# joysticks_right.net
KiCad netlist of a schematic drawn in EAGLE
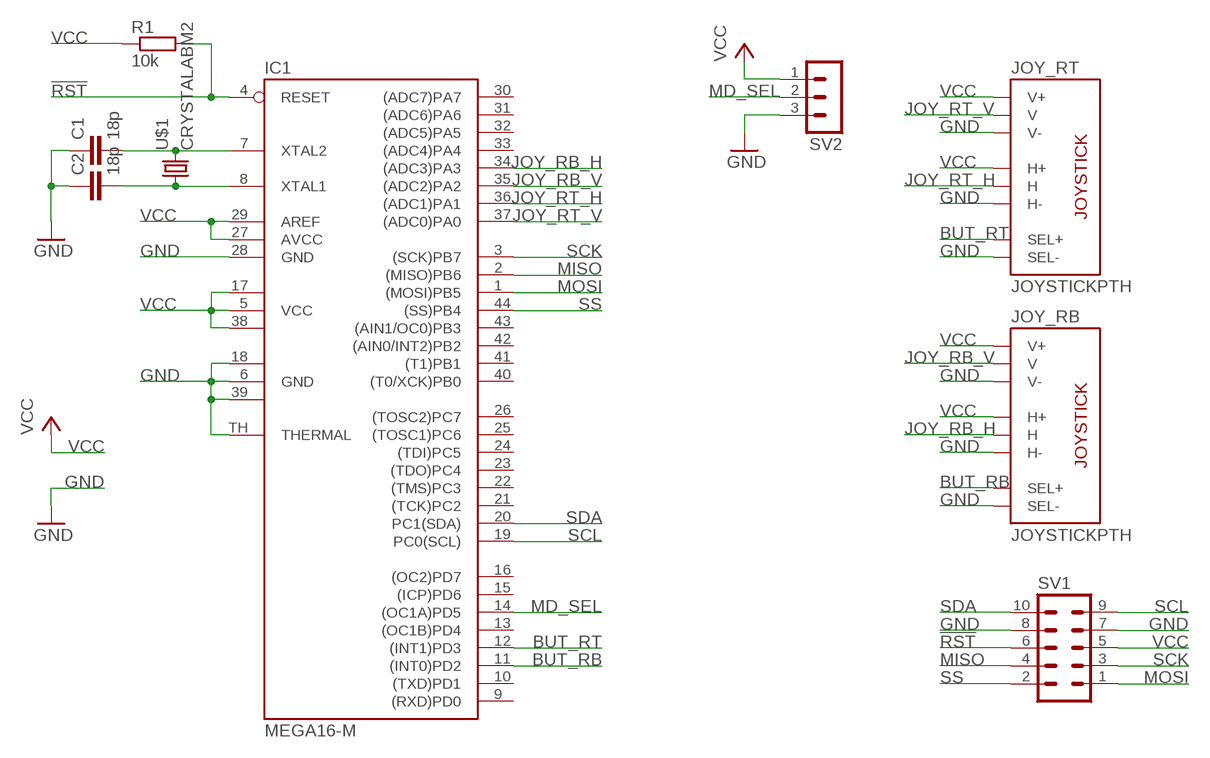
[diagram p0: schematic, sheet 1]

(export (version "E")
  (design (tool "Eeschema 10.0.6"))
  (components
    (comp (ref "C1")
      (value "18p")
      (footprint "eagle-import:C0603")
      (libsource (lib "eagle-import") (part "C-EUC0603"))
    )
    (comp (ref "C2")
      (value "18p")
      (footprint "eagle-import:C0603")
      (libsource (lib "eagle-import") (part "C-EUC0603"))
    )
    (comp (ref "IC1")
      (value "MEGA16-M")
      (footprint "eagle-import:MLF44-TH")
      (fields (field (name "MPN") "ATMEGA16-16MU"))
      (libsource (lib "eagle-import") (part "MEGA16-M"))
    )
    (comp (ref "JOY_RB")
      (value "JOYSTICKPTH")
      (footprint "eagle-import:JOYSTICK")
      (libsource (lib "eagle-import") (part "JOYSTICKPTH"))
    )
    (comp (ref "JOY_RT")
      (value "JOYSTICKPTH")
      (footprint "eagle-import:JOYSTICK")
      (libsource (lib "eagle-import") (part "JOYSTICKPTH"))
    )
    (comp (ref "R1")
      (value "10k")
      (footprint "eagle-import:R0603")
      (libsource (lib "eagle-import") (part "R-EU_R0603"))
    )
    (comp (ref "SV1")
      (value "MA05-2")
      (footprint "eagle-import:MA05-2")
      (libsource (lib "eagle-import") (part "MA05-2"))
    )
    (comp (ref "SV2")
      (value "MA03-1")
      (footprint "eagle-import:MA03-1")
      (libsource (lib "eagle-import") (part "MA03-1"))
    )
    (comp (ref "U$1")
      (value "CRYSTALABM2")
      (footprint "eagle-import:ABM2")
      (libsource (lib "eagle-import") (part "CRYSTALABM2"))
    )
  )
  (nets
    (net (code "1") (name "/BUT_RB") (class "Default")
      (node (ref "IC1") (pin "11") (pinfunction "(INT0)PD2_11") (pintype "bidirectional"))
      (node (ref "JOY_RB") (pin "B1A") (pinfunction "SEL+_B1A") (pintype "bidirectional"))
    )
    (net (code "2") (name "/BUT_RT") (class "Default")
      (node (ref "IC1") (pin "12") (pinfunction "(INT1)PD3_12") (pintype "bidirectional"))
      (node (ref "JOY_RT") (pin "B1A") (pinfunction "SEL+_B1A") (pintype "bidirectional"))
    )
    (net (code "3") (name "/JOY_RB_H") (class "Default")
      (node (ref "IC1") (pin "34") (pinfunction "(ADC3)PA3_34") (pintype "bidirectional"))
      (node (ref "JOY_RB") (pin "H2") (pinfunction "H_H2") (pintype "bidirectional"))
    )
    (net (code "4") (name "/JOY_RB_V") (class "Default")
      (node (ref "IC1") (pin "35") (pinfunction "(ADC2)PA2_35") (pintype "bidirectional"))
      (node (ref "JOY_RB") (pin "V2") (pinfunction "V_V2") (pintype "bidirectional"))
    )
    (net (code "5") (name "/JOY_RT_H") (class "Default")
      (node (ref "IC1") (pin "36") (pinfunction "(ADC1)PA1_36") (pintype "bidirectional"))
      (node (ref "JOY_RT") (pin "H2") (pinfunction "H_H2") (pintype "bidirectional"))
    )
    (net (code "6") (name "/JOY_RT_V") (class "Default")
      (node (ref "IC1") (pin "37") (pinfunction "(ADC0)PA0_37") (pintype "bidirectional"))
      (node (ref "JOY_RT") (pin "V2") (pinfunction "V_V2") (pintype "bidirectional"))
    )
    (net (code "7") (name "/MD_SEL") (class "Default")
      (node (ref "IC1") (pin "14") (pinfunction "(OC1A)PD5_14") (pintype "bidirectional"))
      (node (ref "SV2") (pin "2") (pinfunction "2_2") (pintype "passive"))
    )
    (net (code "8") (name "/MISO") (class "Default")
      (node (ref "IC1") (pin "2") (pinfunction "(MISO)PB6_2") (pintype "bidirectional"))
      (node (ref "SV1") (pin "4") (pinfunction "4_4") (pintype "passive"))
    )
    (net (code "9") (name "/MOSI") (class "Default")
      (node (ref "IC1") (pin "1") (pinfunction "(MOSI)PB5_1") (pintype "bidirectional"))
      (node (ref "SV1") (pin "1") (pinfunction "1_1") (pintype "passive"))
    )
    (net (code "10") (name "/SCK") (class "Default")
      (node (ref "IC1") (pin "3") (pinfunction "(SCK)PB7_3") (pintype "bidirectional"))
      (node (ref "SV1") (pin "3") (pinfunction "3_3") (pintype "passive"))
    )
    (net (code "11") (name "/SCL") (class "Default")
      (node (ref "IC1") (pin "19") (pinfunction "PC0(SCL)_19") (pintype "bidirectional"))
      (node (ref "SV1") (pin "9") (pinfunction "9_9") (pintype "passive"))
    )
    (net (code "12") (name "/SDA") (class "Default")
      (node (ref "IC1") (pin "20") (pinfunction "PC1(SDA)_20") (pintype "bidirectional"))
      (node (ref "SV1") (pin "10") (pinfunction "10_10") (pintype "passive"))
    )
    (net (code "13") (name "/SS") (class "Default")
      (node (ref "IC1") (pin "44") (pinfunction "(SS)PB4_44") (pintype "bidirectional"))
      (node (ref "SV1") (pin "2") (pinfunction "2_2") (pintype "passive"))
    )
    (net (code "14") (name "/~{RST}") (class "Default")
      (node (ref "IC1") (pin "4") (pinfunction "RESET_4") (pintype "input"))
      (node (ref "R1") (pin "2") (pinfunction "2_2") (pintype "passive"))
      (node (ref "SV1") (pin "6") (pinfunction "6_6") (pintype "passive"))
    )
    (net (code "15") (name "GND") (class "Default")
      (node (ref "C1") (pin "1") (pinfunction "1_1") (pintype "passive"))
      (node (ref "C2") (pin "1") (pinfunction "1_1") (pintype "passive"))
      (node (ref "IC1") (pin "18") (pinfunction "GND1_18") (pintype "power_in"))
      (node (ref "IC1") (pin "28") (pinfunction "GND_28") (pintype "power_in"))
      (node (ref "IC1") (pin "39") (pinfunction "GND2_39") (pintype "power_in"))
      (node (ref "IC1") (pin "6") (pinfunction "GND_6") (pintype "power_in"))
      (node (ref "IC1") (pin "TH") (pinfunction "THERMAL_TH") (pintype "input"))
      (node (ref "JOY_RB") (pin "B2A") (pinfunction "SEL-_B2A") (pintype "bidirectional"))
      (node (ref "JOY_RB") (pin "H3") (pinfunction "H-_H3") (pintype "bidirectional"))
      (node (ref "JOY_RB") (pin "V3") (pinfunction "V-_V3") (pintype "bidirectional"))
      (node (ref "JOY_RT") (pin "B2A") (pinfunction "SEL-_B2A") (pintype "bidirectional"))
      (node (ref "JOY_RT") (pin "H3") (pinfunction "H-_H3") (pintype "bidirectional"))
      (node (ref "JOY_RT") (pin "V3") (pinfunction "V-_V3") (pintype "bidirectional"))
      (node (ref "SV1") (pin "7") (pinfunction "7_7") (pintype "passive"))
      (node (ref "SV1") (pin "8") (pinfunction "8_8") (pintype "passive"))
      (node (ref "SV2") (pin "3") (pinfunction "3_3") (pintype "passive"))
    )
    (net (code "16") (name "Net-(IC1-XTAL1)") (class "Default")
      (node (ref "C2") (pin "2") (pinfunction "2_2") (pintype "passive"))
      (node (ref "IC1") (pin "8") (pinfunction "XTAL1_8") (pintype "bidirectional"))
      (node (ref "U$1") (pin "P$1") (pinfunction "1_P$1") (pintype "passive"))
    )
    (net (code "17") (name "Net-(IC1-XTAL2)") (class "Default")
      (node (ref "C1") (pin "2") (pinfunction "2_2") (pintype "passive"))
      (node (ref "IC1") (pin "7") (pinfunction "XTAL2_7") (pintype "bidirectional"))
      (node (ref "U$1") (pin "P$2") (pinfunction "2_P$2") (pintype "passive"))
    )
    (net (code "18") (name "VCC") (class "Default")
      (node (ref "IC1") (pin "17") (pinfunction "VCC1_17") (pintype "power_in"))
      (node (ref "IC1") (pin "27") (pinfunction "AVCC_27") (pintype "power_in"))
      (node (ref "IC1") (pin "29") (pinfunction "AREF_29") (pintype "passive"))
      (node (ref "IC1") (pin "38") (pinfunction "VCC2_38") (pintype "power_in"))
      (node (ref "IC1") (pin "5") (pinfunction "VCC_5") (pintype "power_in"))
      (node (ref "JOY_RB") (pin "H1") (pinfunction "H+_H1") (pintype "bidirectional"))
      (node (ref "JOY_RB") (pin "V1") (pinfunction "V+_V1") (pintype "bidirectional"))
      (node (ref "JOY_RT") (pin "H1") (pinfunction "H+_H1") (pintype "bidirectional"))
      (node (ref "JOY_RT") (pin "V1") (pinfunction "V+_V1") (pintype "bidirectional"))
      (node (ref "R1") (pin "1") (pinfunction "1_1") (pintype "passive"))
      (node (ref "SV1") (pin "5") (pinfunction "5_5") (pintype "passive"))
      (node (ref "SV2") (pin "1") (pinfunction "1_1") (pintype "passive"))
    )
    (net (code "19") (name "unconnected-(IC1-(ADC4)PA4-Pad33)") (class "Default")
      (node (ref "IC1") (pin "33") (pinfunction "(ADC4)PA4_33") (pintype "bidirectional"))
    )
    (net (code "20") (name "unconnected-(IC1-(ADC5)PA5-Pad32)") (class "Default")
      (node (ref "IC1") (pin "32") (pinfunction "(ADC5)PA5_32") (pintype "bidirectional"))
    )
    (net (code "21") (name "unconnected-(IC1-(ADC6)PA6-Pad31)") (class "Default")
      (node (ref "IC1") (pin "31") (pinfunction "(ADC6)PA6_31") (pintype "bidirectional"))
    )
    (net (code "22") (name "unconnected-(IC1-(ADC7)PA7-Pad30)") (class "Default")
      (node (ref "IC1") (pin "30") (pinfunction "(ADC7)PA7_30") (pintype "bidirectional"))
    )
    (net (code "23") (name "unconnected-(IC1-(AIN0{slash}INT2)PB2-Pad42)") (class "Default")
      (node (ref "IC1") (pin "42") (pinfunction "(AIN0/INT2)PB2_42") (pintype "bidirectional"))
    )
    (net (code "24") (name "unconnected-(IC1-(AIN1{slash}OC0)PB3-Pad43)") (class "Default")
      (node (ref "IC1") (pin "43") (pinfunction "(AIN1/OC0)PB3_43") (pintype "bidirectional"))
    )
    (net (code "25") (name "unconnected-(IC1-(ICP)PD6-Pad15)") (class "Default")
      (node (ref "IC1") (pin "15") (pinfunction "(ICP)PD6_15") (pintype "bidirectional"))
    )
    (net (code "26") (name "unconnected-(IC1-(OC1B)PD4-Pad13)") (class "Default")
      (node (ref "IC1") (pin "13") (pinfunction "(OC1B)PD4_13") (pintype "bidirectional"))
    )
    (net (code "27") (name "unconnected-(IC1-(OC2)PD7-Pad16)") (class "Default")
      (node (ref "IC1") (pin "16") (pinfunction "(OC2)PD7_16") (pintype "bidirectional"))
    )
    (net (code "28") (name "unconnected-(IC1-(RXD)PD0-Pad9)") (class "Default")
      (node (ref "IC1") (pin "9") (pinfunction "(RXD)PD0_9") (pintype "bidirectional"))
    )
    (net (code "29") (name "unconnected-(IC1-(T0{slash}XCK)PB0-Pad40)") (class "Default")
      (node (ref "IC1") (pin "40") (pinfunction "(T0/XCK)PB0_40") (pintype "bidirectional"))
    )
    (net (code "30") (name "unconnected-(IC1-(T1)PB1-Pad41)") (class "Default")
      (node (ref "IC1") (pin "41") (pinfunction "(T1)PB1_41") (pintype "bidirectional"))
    )
    (net (code "31") (name "unconnected-(IC1-(TCK)PC2-Pad21)") (class "Default")
      (node (ref "IC1") (pin "21") (pinfunction "(TCK)PC2_21") (pintype "bidirectional"))
    )
    (net (code "32") (name "unconnected-(IC1-(TDI)PC5-Pad24)") (class "Default")
      (node (ref "IC1") (pin "24") (pinfunction "(TDI)PC5_24") (pintype "bidirectional"))
    )
    (net (code "33") (name "unconnected-(IC1-(TDO)PC4-Pad23)") (class "Default")
      (node (ref "IC1") (pin "23") (pinfunction "(TDO)PC4_23") (pintype "bidirectional"))
    )
    (net (code "34") (name "unconnected-(IC1-(TMS)PC3-Pad22)") (class "Default")
      (node (ref "IC1") (pin "22") (pinfunction "(TMS)PC3_22") (pintype "bidirectional"))
    )
    (net (code "35") (name "unconnected-(IC1-(TOSC1)PC6-Pad25)") (class "Default")
      (node (ref "IC1") (pin "25") (pinfunction "(TOSC1)PC6_25") (pintype "bidirectional"))
    )
    (net (code "36") (name "unconnected-(IC1-(TOSC2)PC7-Pad26)") (class "Default")
      (node (ref "IC1") (pin "26") (pinfunction "(TOSC2)PC7_26") (pintype "bidirectional"))
    )
    (net (code "37") (name "unconnected-(IC1-(TXD)PD1-Pad10)") (class "Default")
      (node (ref "IC1") (pin "10") (pinfunction "(TXD)PD1_10") (pintype "bidirectional"))
    )
  )
)
